# diapers1.net
KiCad netlist of a schematic drawn in Altium Designer
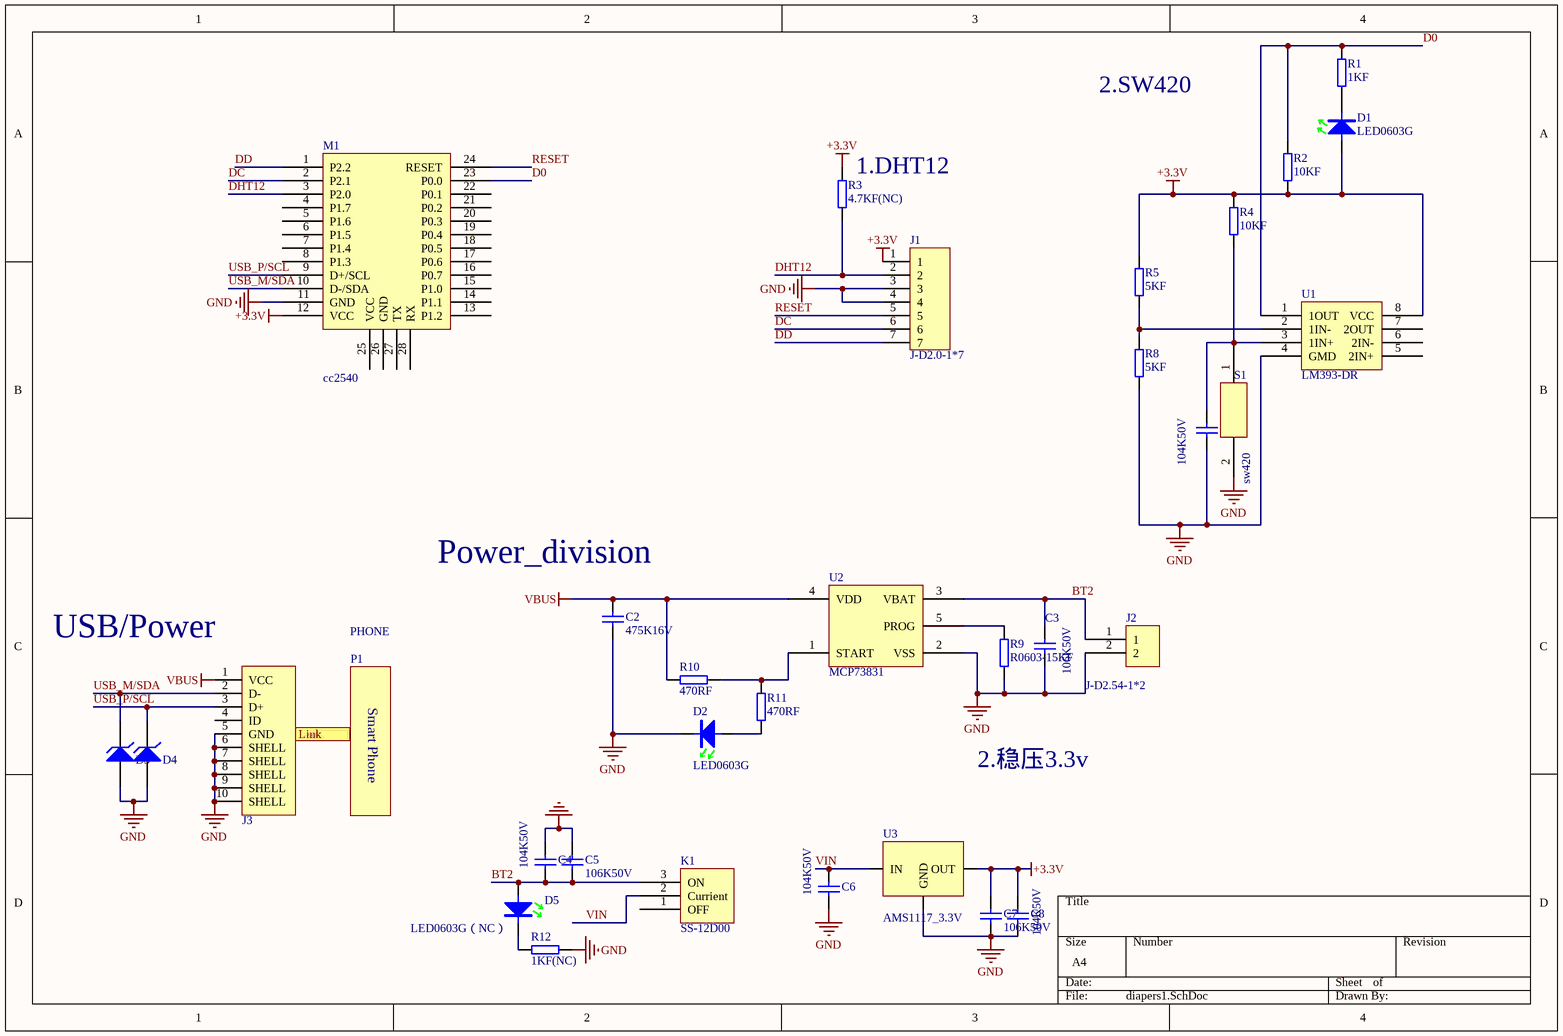
[diagram p0: diapers1.SchDoc]

(export (version "E")
  (design (tool "Eeschema 10.0.6"))
  (components
    (comp (ref "C1")
      (value "104K50V")
      (footprint "C0603")
      (description "贴片电容-陶瓷")
      (libsource (lib "Capacitor") (part "C0603X7R-104K50V"))
    )
    (comp (ref "C2")
      (value "475K16V")
      (footprint "C0603")
      (description "贴片电容-陶瓷")
      (libsource (lib "Capacitor") (part "C0603X7R-475K16V"))
    )
    (comp (ref "C3")
      (value "106K50V")
      (footprint "C0603")
      (description "贴片电容-陶瓷")
      (libsource (lib "Capacitor") (part "C0603X7R-106K50V"))
    )
    (comp (ref "C4")
      (value "104K50V")
      (footprint "C0603")
      (description "贴片电容-陶瓷")
      (libsource (lib "Capacitor") (part "C0603X7R-104K50V"))
    )
    (comp (ref "C5")
      (value "106K50V")
      (footprint "C0603")
      (description "贴片电容-陶瓷")
      (libsource (lib "Capacitor") (part "C0603X7R-106K50V"))
    )
    (comp (ref "C6")
      (value "104K50V")
      (footprint "C0603")
      (description "贴片电容-陶瓷")
      (libsource (lib "Capacitor") (part "C0603X7R-104K50V"))
    )
    (comp (ref "C7")
      (value "106K50V")
      (footprint "C0603")
      (description "贴片电容-陶瓷")
      (libsource (lib "Capacitor") (part "C0603X7R-106K50V"))
    )
    (comp (ref "C8")
      (value "104K50V")
      (footprint "C0603")
      (description "贴片电容-陶瓷")
      (libsource (lib "Capacitor") (part "C0603X7R-104K50V"))
    )
    (comp (ref "D1")
      (value "LED0603G")
      (footprint "D-LED0603G")
      (description "贴片二极管-LED")
      (libsource (lib "Diode") (part "DLED-0603-G"))
    )
    (comp (ref "D2")
      (value "LED0603G")
      (footprint "D-LED0603G")
      (description "贴片二极管-LED")
      (libsource (lib "Diode") (part "DLED-0603-G"))
    )
    (comp (ref "D3")
      (value "ESDA_TR1/0603")
      (footprint "HS_0603D")
      (description "Zener Diode")
      (fields (field (name "PUBLISHER") "*"))
      (libsource (lib "aiwacV2.0") (part "D Zener"))
    )
    (comp (ref "D4")
      (value "ESDA_TR1/0603")
      (footprint "HS_0603D")
      (description "Zener Diode")
      (fields (field (name "PUBLISHER") "*"))
      (libsource (lib "aiwacV2.0") (part "D Zener"))
    )
    (comp (ref "D5")
      (value "LED0603G（NC）")
      (footprint "D-LED0603G")
      (description "贴片二极管-LED")
      (libsource (lib "aiwacV2.0") (part "DLED-0603-G"))
    )
    (comp (ref "J1")
      (value "J-D2.0-1*7")
      (footprint "D-2.0-1*7")
      (libsource (lib "Connector") (part "J-D2.0-1*7单排"))
    )
    (comp (ref "J2")
      (value "J-D2.54-1*2")
      (footprint "D2.54-1*2P")
      (libsource (lib "Connector") (part "J-D2.54-1*2单排"))
    )
    (comp (ref "J3")
      (value "USB-MINI-SOCKET")
      (footprint "MICRO-USB - 5.9")
      (description "USB-A卧式插座")
      (libsource (lib "epic2") (part "J-USB-MINI-SOCKET"))
    )
    (comp (ref "K1")
      (value "SS-12D00")
      (footprint "SS-12D00")
      (libsource (lib "Key") (part "SS-12D00(1P2T) 立式 柄高5MM"))
    )
    (comp (ref "M1") (value "cc2540") (libsource (lib "diapers1") (part "cc2540")))
    (comp (ref "P1") (value "PHONE") (libsource (lib "epic") (part "PHONE")))
    (comp (ref "R1")
      (value "1KF")
      (footprint "R0603")
      (description "贴片电阻-通用")
      (libsource (lib "Resistor") (part "R0603-1KF"))
    )
    (comp (ref "R2")
      (value "10KF")
      (footprint "R0603")
      (description "贴片电阻-通用")
      (libsource (lib "Resistor") (part "R0603-10KF"))
    )
    (comp (ref "R3")
      (value "4.7KF(NC)")
      (footprint "R0603")
      (description "贴片电阻-通用")
      (libsource (lib "Resistor") (part "R0603-4.7KF"))
    )
    (comp (ref "R4")
      (value "10KF")
      (footprint "R0603")
      (description "贴片电阻-通用")
      (libsource (lib "Resistor") (part "R0603-10KF"))
    )
    (comp (ref "R5")
      (value "5KF")
      (footprint "R0603")
      (description "贴片电阻-通用")
      (libsource (lib "Resistor") (part "R0603-10KF"))
    )
    (comp (ref "R8")
      (value "5KF")
      (footprint "R0603")
      (description "贴片电阻-通用")
      (libsource (lib "Resistor") (part "R0603-10KF"))
    )
    (comp (ref "R9")
      (value "R0603-15KF")
      (footprint "R0603")
      (description "贴片电容-通用")
      (libsource (lib "Resistor") (part "R0603-15KF"))
    )
    (comp (ref "R10")
      (value "470RF")
      (footprint "R0603")
      (description "贴片电阻-通用")
      (libsource (lib "Resistor") (part "R0603-470RF"))
    )
    (comp (ref "R11")
      (value "470RF")
      (footprint "R0603")
      (description "贴片电阻-通用")
      (libsource (lib "Resistor") (part "R0603-470RF"))
    )
    (comp (ref "R12")
      (value "1KF(NC)")
      (footprint "R0603")
      (description "贴片电阻-通用")
      (libsource (lib "Resistor") (part "R0603-1KF"))
    )
    (comp (ref "S1")
      (value "sw420")
      (footprint "sw420")
      (description "常闭振动传感器")
      (libsource (lib "sensor") (part "sw420"))
    )
    (comp (ref "U1")
      (value "LM393-DR")
      (footprint "LM393")
      (description "双路比较器")
      (libsource (lib "IC") (part "LM393-DR"))
    )
    (comp (ref "U2")
      (value "MCP73831")
      (footprint "SOT23-5N")
      (description "charge IC")
      (libsource (lib "IC") (part "MCP73831"))
    )
    (comp (ref "U3")
      (value "AMS1117_3.3V")
      (footprint "SOT-223")
      (libsource (lib "IC") (part "AMS1117-3.3V"))
    )
  )
  (nets
    (net (code "1") (name "+3.3V") (class "Default")
      (node (ref "C7") (pin "2") (pinfunction "2_2") (pintype "passive"))
      (node (ref "C8") (pin "1") (pinfunction "1_1") (pintype "passive"))
      (node (ref "D1") (pin "1") (pinfunction "1_1") (pintype "passive"))
      (node (ref "J1") (pin "1") (pinfunction "1_1") (pintype "passive"))
      (node (ref "M1") (pin "12") (pinfunction "VCC_12") (pintype "passive"))
      (node (ref "R2") (pin "1") (pinfunction "1_1") (pintype "passive"))
      (node (ref "R3") (pin "2") (pinfunction "2_2") (pintype "passive"))
      (node (ref "R4") (pin "2") (pinfunction "2_2") (pintype "passive"))
      (node (ref "R5") (pin "2") (pinfunction "2_2") (pintype "passive"))
      (node (ref "U1") (pin "8") (pinfunction "VCC_8") (pintype "passive"))
      (node (ref "U3") (pin "2") (pinfunction "OUT_2") (pintype "passive"))
    )
    (net (code "2") (name "/BT2") (class "Default")
      (node (ref "C3") (pin "1") (pinfunction "1_1") (pintype "passive"))
      (node (ref "C4") (pin "2") (pinfunction "2_2") (pintype "passive"))
      (node (ref "C5") (pin "1") (pinfunction "1_1") (pintype "passive"))
      (node (ref "D5") (pin "1") (pinfunction "1_1") (pintype "passive"))
      (node (ref "J2") (pin "1") (pinfunction "1_1") (pintype "passive"))
      (node (ref "K1") (pin "3") (pinfunction "ON_3") (pintype "passive"))
      (node (ref "U2") (pin "3") (pinfunction "VBAT_3") (pintype "passive"))
    )
    (net (code "3") (name "/D0") (class "Default")
      (node (ref "M1") (pin "23") (pinfunction "P0.0_23") (pintype "passive"))
      (node (ref "R1") (pin "1") (pinfunction "1_1") (pintype "passive"))
      (node (ref "R2") (pin "2") (pinfunction "2_2") (pintype "passive"))
      (node (ref "U1") (pin "1") (pinfunction "1OUT_1") (pintype "passive"))
    )
    (net (code "4") (name "/DC") (class "Default")
      (node (ref "J1") (pin "6") (pinfunction "6_6") (pintype "passive"))
      (node (ref "M1") (pin "2") (pinfunction "P2.1_2") (pintype "passive"))
    )
    (net (code "5") (name "/DD") (class "Default")
      (node (ref "J1") (pin "7") (pinfunction "7_7") (pintype "passive"))
      (node (ref "M1") (pin "1") (pinfunction "P2.2_1") (pintype "passive"))
    )
    (net (code "6") (name "/DHT12") (class "Default")
      (node (ref "J1") (pin "2") (pinfunction "2_2") (pintype "passive"))
      (node (ref "M1") (pin "3") (pinfunction "P2.0_3") (pintype "passive"))
      (node (ref "R3") (pin "1") (pinfunction "1_1") (pintype "passive"))
    )
    (net (code "8") (name "/RESET") (class "Default")
      (node (ref "J1") (pin "5") (pinfunction "5_5") (pintype "passive"))
      (node (ref "M1") (pin "24") (pinfunction "RESET_24") (pintype "passive"))
    )
    (net (code "9") (name "/USB_M{slash}SDA") (class "Default")
      (node (ref "D3") (pin "2") (pinfunction "K_2") (pintype "passive"))
      (node (ref "J3") (pin "2") (pinfunction "D-_2") (pintype "passive"))
      (node (ref "M1") (pin "10") (pinfunction "D-/SDA_10") (pintype "passive"))
    )
    (net (code "10") (name "/USB_P{slash}SCL") (class "Default")
      (node (ref "D4") (pin "2") (pinfunction "K_2") (pintype "passive"))
      (node (ref "J3") (pin "3") (pinfunction "D+_3") (pintype "passive"))
      (node (ref "M1") (pin "9") (pinfunction "D+/SCL_9") (pintype "passive"))
    )
    (net (code "11") (name "/VIN") (class "Default")
      (node (ref "C6") (pin "1") (pinfunction "1_1") (pintype "passive"))
      (node (ref "K1") (pin "2") (pinfunction "Currient_2") (pintype "passive"))
      (node (ref "U3") (pin "3") (pinfunction "IN_3") (pintype "passive"))
    )
    (net (code "12") (name "GND") (class "Default")
      (node (ref "C1") (pin "2") (pinfunction "2_2") (pintype "passive"))
      (node (ref "C2") (pin "2") (pinfunction "2_2") (pintype "passive"))
      (node (ref "C3") (pin "2") (pinfunction "2_2") (pintype "passive"))
      (node (ref "C4") (pin "1") (pinfunction "1_1") (pintype "passive"))
      (node (ref "C5") (pin "2") (pinfunction "2_2") (pintype "passive"))
      (node (ref "C6") (pin "2") (pinfunction "2_2") (pintype "passive"))
      (node (ref "C7") (pin "1") (pinfunction "1_1") (pintype "passive"))
      (node (ref "C8") (pin "2") (pinfunction "2_2") (pintype "passive"))
      (node (ref "D2") (pin "2") (pinfunction "2_2") (pintype "passive"))
      (node (ref "D3") (pin "1") (pinfunction "A_1") (pintype "passive"))
      (node (ref "D4") (pin "1") (pinfunction "A_1") (pintype "passive"))
      (node (ref "J1") (pin "3") (pinfunction "3_3") (pintype "passive"))
      (node (ref "J1") (pin "4") (pinfunction "4_4") (pintype "passive"))
      (node (ref "J2") (pin "2") (pinfunction "2_2") (pintype "passive"))
      (node (ref "J3") (pin "10") (pinfunction "SHELL_10") (pintype "passive"))
      (node (ref "J3") (pin "5") (pinfunction "GND_5") (pintype "passive"))
      (node (ref "J3") (pin "6") (pinfunction "SHELL_6") (pintype "passive"))
      (node (ref "J3") (pin "7") (pinfunction "SHELL_7") (pintype "passive"))
      (node (ref "J3") (pin "8") (pinfunction "SHELL_8") (pintype "passive"))
      (node (ref "J3") (pin "9") (pinfunction "SHELL_9") (pintype "passive"))
      (node (ref "M1") (pin "11") (pinfunction "GND_11") (pintype "passive"))
      (node (ref "R12") (pin "2") (pinfunction "2_2") (pintype "passive"))
      (node (ref "R8") (pin "1") (pinfunction "1_1") (pintype "passive"))
      (node (ref "R9") (pin "1") (pinfunction "1_1") (pintype "passive"))
      (node (ref "U1") (pin "4") (pinfunction "GMD_4") (pintype "passive"))
      (node (ref "U2") (pin "2") (pinfunction "VSS_2") (pintype "passive"))
      (node (ref "U3") (pin "1") (pinfunction "GND_1") (pintype "passive"))
    )
    (net (code "13") (name "Net-(D1-Pad2)") (class "Default")
      (node (ref "D1") (pin "2") (pinfunction "2_2") (pintype "passive"))
      (node (ref "R1") (pin "2") (pinfunction "2_2") (pintype "passive"))
    )
    (net (code "14") (name "Net-(D2-Pad1)") (class "Default")
      (node (ref "D2") (pin "1") (pinfunction "1_1") (pintype "passive"))
      (node (ref "R11") (pin "1") (pinfunction "1_1") (pintype "passive"))
    )
    (net (code "15") (name "Net-(D5-Pad2)") (class "Default")
      (node (ref "D5") (pin "2") (pinfunction "2_2") (pintype "passive"))
      (node (ref "R12") (pin "1") (pinfunction "1_1") (pintype "passive"))
    )
    (net (code "16") (name "Net-(U1-1IN+)") (class "Default")
      (node (ref "C1") (pin "1") (pinfunction "1_1") (pintype "passive"))
      (node (ref "R4") (pin "1") (pinfunction "1_1") (pintype "passive"))
      (node (ref "S1") (pin "1") (pinfunction "1_1") (pintype "passive"))
      (node (ref "U1") (pin "3") (pinfunction "1IN+_3") (pintype "passive"))
    )
    (net (code "17") (name "Net-(U1-1IN-)") (class "Default")
      (node (ref "R5") (pin "1") (pinfunction "1_1") (pintype "passive"))
      (node (ref "R8") (pin "2") (pinfunction "2_2") (pintype "passive"))
      (node (ref "U1") (pin "2") (pinfunction "1IN-_2") (pintype "passive"))
    )
    (net (code "18") (name "Net-(U2-PROG)") (class "Default")
      (node (ref "R9") (pin "2") (pinfunction "2_2") (pintype "passive"))
      (node (ref "U2") (pin "5") (pinfunction "PROG_5") (pintype "passive"))
    )
    (net (code "19") (name "Net-(U2-START)") (class "Default")
      (node (ref "R10") (pin "2") (pinfunction "2_2") (pintype "passive"))
      (node (ref "R11") (pin "2") (pinfunction "2_2") (pintype "passive"))
      (node (ref "U2") (pin "1") (pinfunction "START_1") (pintype "passive"))
    )
    (net (code "20") (name "VBUS") (class "Default")
      (node (ref "C2") (pin "1") (pinfunction "1_1") (pintype "passive"))
      (node (ref "J3") (pin "1") (pinfunction "VCC_1") (pintype "passive"))
      (node (ref "R10") (pin "1") (pinfunction "1_1") (pintype "passive"))
      (node (ref "U2") (pin "4") (pinfunction "VDD_4") (pintype "passive"))
    )
    (net (code "21") (name "unconnected-(J3-ID-Pad4)") (class "Default")
      (node (ref "J3") (pin "4") (pinfunction "ID_4") (pintype "passive"))
    )
    (net (code "22") (name "unconnected-(K1-OFF-Pad1)") (class "Default")
      (node (ref "K1") (pin "1") (pinfunction "OFF_1") (pintype "passive"))
    )
    (net (code "23") (name "unconnected-(M1-GND-Pad26)") (class "Default")
      (node (ref "M1") (pin "26") (pinfunction "GND_26") (pintype "passive"))
    )
    (net (code "24") (name "unconnected-(M1-P0.1-Pad22)") (class "Default")
      (node (ref "M1") (pin "22") (pinfunction "P0.1_22") (pintype "passive"))
    )
    (net (code "25") (name "unconnected-(M1-P0.2-Pad21)") (class "Default")
      (node (ref "M1") (pin "21") (pinfunction "P0.2_21") (pintype "passive"))
    )
    (net (code "26") (name "unconnected-(M1-P0.3-Pad20)") (class "Default")
      (node (ref "M1") (pin "20") (pinfunction "P0.3_20") (pintype "passive"))
    )
    (net (code "27") (name "unconnected-(M1-P0.4-Pad19)") (class "Default")
      (node (ref "M1") (pin "19") (pinfunction "P0.4_19") (pintype "passive"))
    )
    (net (code "28") (name "unconnected-(M1-P0.5-Pad18)") (class "Default")
      (node (ref "M1") (pin "18") (pinfunction "P0.5_18") (pintype "passive"))
    )
    (net (code "29") (name "unconnected-(M1-P0.6-Pad17)") (class "Default")
      (node (ref "M1") (pin "17") (pinfunction "P0.6_17") (pintype "passive"))
    )
    (net (code "30") (name "unconnected-(M1-P0.7-Pad16)") (class "Default")
      (node (ref "M1") (pin "16") (pinfunction "P0.7_16") (pintype "passive"))
    )
    (net (code "31") (name "unconnected-(M1-P1.0-Pad15)") (class "Default")
      (node (ref "M1") (pin "15") (pinfunction "P1.0_15") (pintype "passive"))
    )
    (net (code "32") (name "unconnected-(M1-P1.1-Pad14)") (class "Default")
      (node (ref "M1") (pin "14") (pinfunction "P1.1_14") (pintype "passive"))
    )
    (net (code "33") (name "unconnected-(M1-P1.2-Pad13)") (class "Default")
      (node (ref "M1") (pin "13") (pinfunction "P1.2_13") (pintype "passive"))
    )
    (net (code "34") (name "unconnected-(M1-P1.3-Pad8)") (class "Default")
      (node (ref "M1") (pin "8") (pinfunction "P1.3_8") (pintype "passive"))
    )
    (net (code "35") (name "unconnected-(M1-P1.4-Pad7)") (class "Default")
      (node (ref "M1") (pin "7") (pinfunction "P1.4_7") (pintype "passive"))
    )
    (net (code "36") (name "unconnected-(M1-P1.5-Pad6)") (class "Default")
      (node (ref "M1") (pin "6") (pinfunction "P1.5_6") (pintype "passive"))
    )
    (net (code "37") (name "unconnected-(M1-P1.6-Pad5)") (class "Default")
      (node (ref "M1") (pin "5") (pinfunction "P1.6_5") (pintype "passive"))
    )
    (net (code "38") (name "unconnected-(M1-P1.7-Pad4)") (class "Default")
      (node (ref "M1") (pin "4") (pinfunction "P1.7_4") (pintype "passive"))
    )
    (net (code "39") (name "unconnected-(M1-RX-Pad28)") (class "Default")
      (node (ref "M1") (pin "28") (pinfunction "RX_28") (pintype "passive"))
    )
    (net (code "40") (name "unconnected-(M1-TX-Pad27)") (class "Default")
      (node (ref "M1") (pin "27") (pinfunction "TX_27") (pintype "passive"))
    )
    (net (code "41") (name "unconnected-(M1-VCC-Pad25)") (class "Default")
      (node (ref "M1") (pin "25") (pinfunction "VCC_25") (pintype "passive"))
    )
    (net (code "42") (name "unconnected-(S1-Pad2)") (class "Default")
      (node (ref "S1") (pin "2") (pinfunction "2_2") (pintype "passive"))
    )
    (net (code "43") (name "unconnected-(U1-2IN+-Pad5)") (class "Default")
      (node (ref "U1") (pin "5") (pinfunction "2IN+_5") (pintype "passive"))
    )
    (net (code "44") (name "unconnected-(U1-2IN--Pad6)") (class "Default")
      (node (ref "U1") (pin "6") (pinfunction "2IN-_6") (pintype "passive"))
    )
    (net (code "45") (name "unconnected-(U1-2OUT-Pad7)") (class "Default")
      (node (ref "U1") (pin "7") (pinfunction "2OUT_7") (pintype "passive"))
    )
  )
)
